# In_put.net
KiCad netlist of a schematic drawn in Altium Designer
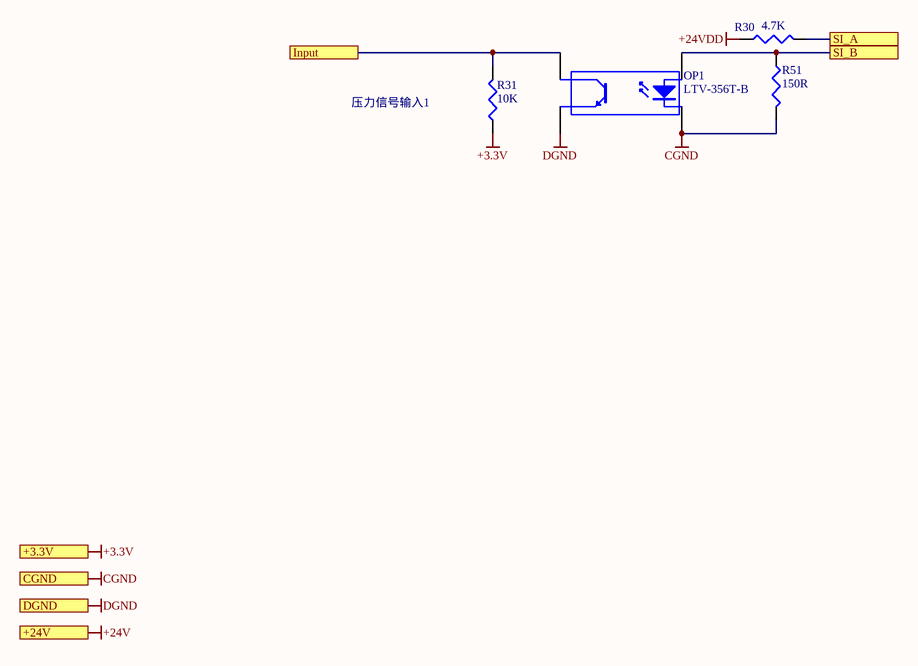
[diagram p0: In_put .SchDoc]

(export (version "E")
  (design (tool "Eeschema 10.0.6"))
  (components
    (comp (ref "OP1")
      (value "LTV-356T-B")
      (footprint "TLV-356")
      (description "品牌名称\r\nLITEON(光宝)\r\n商品型号\r\n\r\nLTV-356T-B\r\n商品编号\r\n\r\nC10804\r\n商品封装\r\n\r\nSOP-4-2.54mm")
      (libsource (lib "*") (part "OPTOISO1"))
    )
    (comp (ref "R30")
      (value "4.7K")
      (footprint "0805R")
      (description "电阻类型：厚膜电阻 阻值：4.7kΩ 精度：±1% 功率：125mW 温度系数：±100ppm/℃")
      (libsource (lib "*") (part "RES1"))
    )
    (comp (ref "R31")
      (value "10K")
      (footprint "0805R")
      (description "品牌： UNI-ROYAL(厚声) 型号： 0805W8F1002T5E 电阻类型：厚膜电阻 阻值：10kΩ 精度：±1% 功率：125mW 温度系数：±100ppm/℃")
      (libsource (lib "*") (part "RES1"))
    )
    (comp (ref "R51")
      (value "150R")
      (footprint "0805R")
      (description "电阻类型：厚膜电阻 阻值：4.7kΩ 精度：±1% 功率：125mW 温度系数：±100ppm/℃")
      (libsource (lib "*") (part "RES1"))
    )
  )
  (nets
    (net (code "1") (name "+3.3V") (class "Default")
      (node (ref "R31") (pin "1") (pinfunction "1_1") (pintype "passive"))
    )
    (net (code "3") (name "+24VDD") (class "Default")
      (node (ref "R30") (pin "1") (pinfunction "1_1") (pintype "passive"))
    )
    (net (code "4") (name "/Input") (class "Default")
      (node (ref "OP1") (pin "4") (pinfunction "C_4") (pintype "passive"))
      (node (ref "R31") (pin "2") (pinfunction "2_2") (pintype "passive"))
    )
    (net (code "5") (name "/SI_A") (class "Default")
      (node (ref "R30") (pin "2") (pinfunction "2_2") (pintype "passive"))
    )
    (net (code "6") (name "/SI_B") (class "Default")
      (node (ref "OP1") (pin "1") (pinfunction "A_1") (pintype "passive"))
      (node (ref "R51") (pin "1") (pinfunction "1_1") (pintype "passive"))
    )
    (net (code "7") (name "CGND") (class "Default")
      (node (ref "OP1") (pin "2") (pinfunction "K_2") (pintype "passive"))
      (node (ref "R51") (pin "2") (pinfunction "2_2") (pintype "passive"))
    )
    (net (code "8") (name "DGND") (class "Default")
      (node (ref "OP1") (pin "3") (pinfunction "E_3") (pintype "passive"))
    )
  )
)
